# DisplayArray.net
KiCad netlist of a schematic drawn in EAGLE
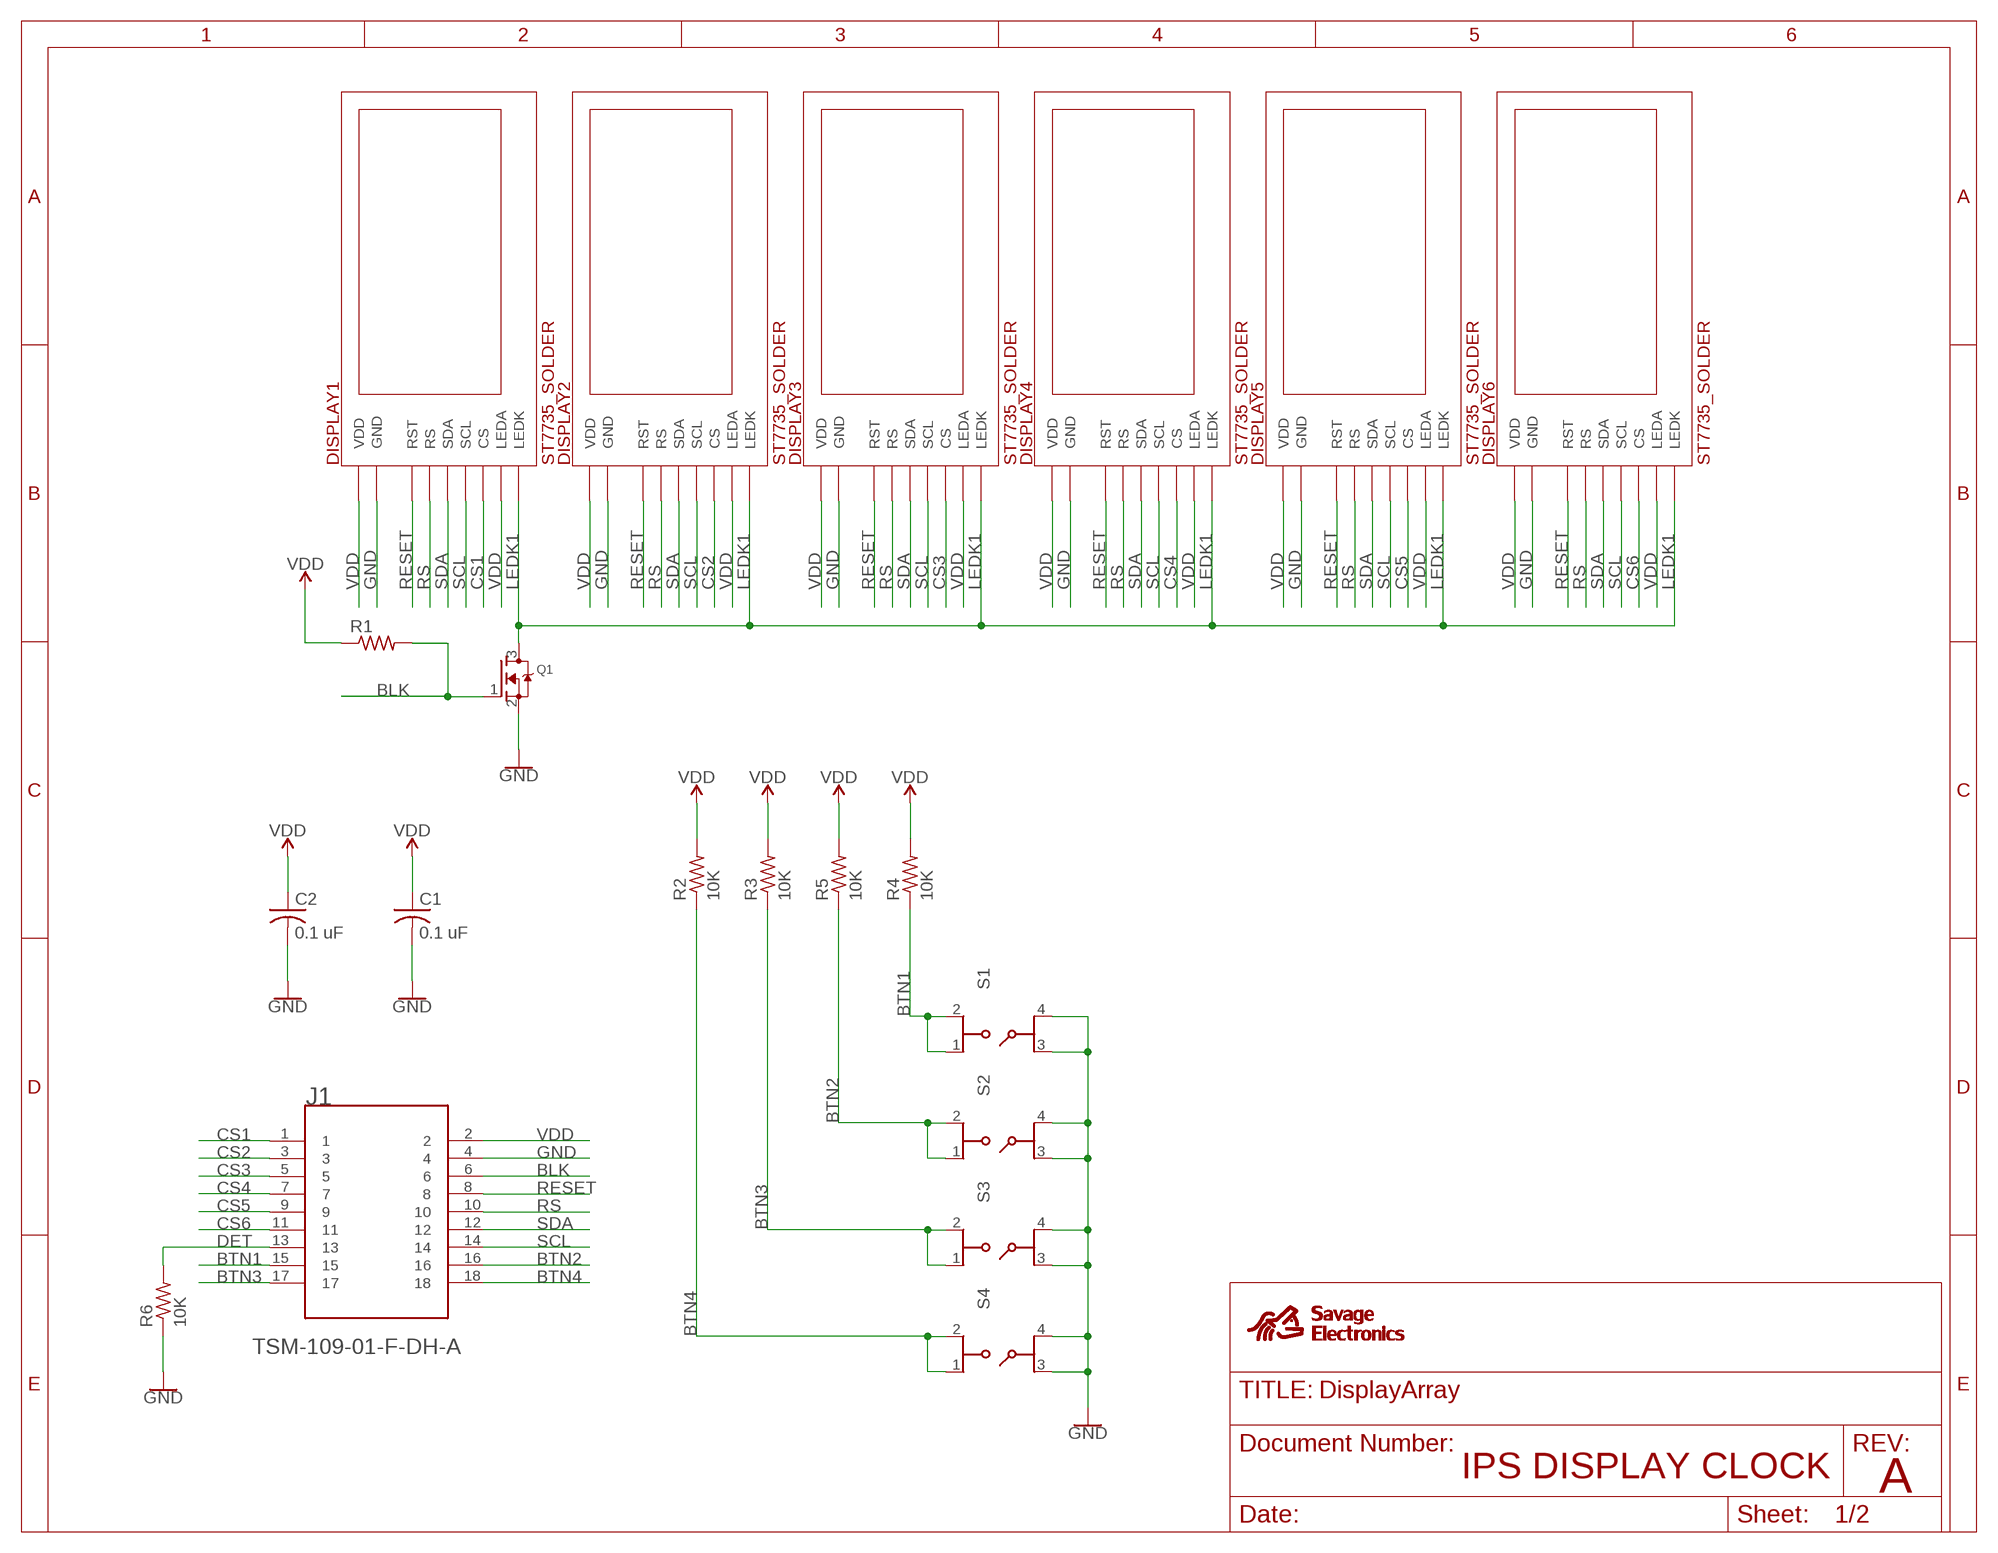
[diagram p0: schematic, sheet 1]

(export (version "E")
  (design (tool "Eeschema 10.0.6"))
  (components
    (comp (ref "C1")
      (value "0.1 uF")
      (footprint "eagle-import:C0603")
      (libsource (lib "eagle-import") (part "C-USC0603"))
    )
    (comp (ref "C2")
      (value "0.1 uF")
      (footprint "eagle-import:C0603")
      (libsource (lib "eagle-import") (part "C-USC0603"))
    )
    (comp (ref "DISPLAY1")
      (value "ST7735_SOLDER")
      (footprint "eagle-import:IPSLCD096_SOLDER")
      (libsource (lib "eagle-import") (part "ST7735_SOLDER"))
    )
    (comp (ref "DISPLAY2")
      (value "ST7735_SOLDER")
      (footprint "eagle-import:IPSLCD096_SOLDER")
      (libsource (lib "eagle-import") (part "ST7735_SOLDER"))
    )
    (comp (ref "DISPLAY3")
      (value "ST7735_SOLDER")
      (footprint "eagle-import:IPSLCD096_SOLDER")
      (libsource (lib "eagle-import") (part "ST7735_SOLDER"))
    )
    (comp (ref "DISPLAY4")
      (value "ST7735_SOLDER")
      (footprint "eagle-import:IPSLCD096_SOLDER")
      (libsource (lib "eagle-import") (part "ST7735_SOLDER"))
    )
    (comp (ref "DISPLAY5")
      (value "ST7735_SOLDER")
      (footprint "eagle-import:IPSLCD096_SOLDER")
      (libsource (lib "eagle-import") (part "ST7735_SOLDER"))
    )
    (comp (ref "DISPLAY6")
      (value "ST7735_SOLDER")
      (footprint "eagle-import:IPSLCD096_SOLDER")
      (libsource (lib "eagle-import") (part "ST7735_SOLDER"))
    )
    (comp (ref "J1")
      (value "TSM-109-01-F-DH-A")
      (footprint "eagle-import:SAMTEC-TSM-109-02-X-DH-A")
      (libsource (lib "eagle-import") (part "SAMTEC-TSM-109-02-X-DH-AJ"))
    )
    (comp (ref "Q1")
      (value "MOSFET-NREFLOW")
      (footprint "eagle-import:SOT23")
      (libsource (lib "eagle-import") (part "MOSFET-NREFLOW"))
    )
    (comp (ref "R1")
      (value "R-US_R0805")
      (footprint "eagle-import:R0805")
      (libsource (lib "eagle-import") (part "R-US_R0805"))
    )
    (comp (ref "R2")
      (value "10K")
      (footprint "eagle-import:R0805")
      (libsource (lib "eagle-import") (part "R-US_R0805"))
    )
    (comp (ref "R3")
      (value "10K")
      (footprint "eagle-import:R0805")
      (libsource (lib "eagle-import") (part "R-US_R0805"))
    )
    (comp (ref "R4")
      (value "10K")
      (footprint "eagle-import:R0805")
      (libsource (lib "eagle-import") (part "R-US_R0805"))
    )
    (comp (ref "R5")
      (value "10K")
      (footprint "eagle-import:R0805")
      (libsource (lib "eagle-import") (part "R-US_R0805"))
    )
    (comp (ref "R6")
      (value "10K")
      (footprint "eagle-import:R0805")
      (libsource (lib "eagle-import") (part "R-US_R0805"))
    )
    (comp (ref "S1")
      (value "434123025826")
      (footprint "eagle-import:434123025826")
      (libsource (lib "eagle-import") (part "434123025826"))
    )
    (comp (ref "S2")
      (value "434123025826")
      (footprint "eagle-import:434123025826")
      (libsource (lib "eagle-import") (part "434123025826"))
    )
    (comp (ref "S3")
      (value "434123025826")
      (footprint "eagle-import:434123025826")
      (libsource (lib "eagle-import") (part "434123025826"))
    )
    (comp (ref "S4")
      (value "434123025826")
      (footprint "eagle-import:434123025826")
      (libsource (lib "eagle-import") (part "434123025826"))
    )
    (comp (ref "U$3")
      (value "SE_SMALL_SILK")
      (footprint "eagle-import:SE_SMALL_SILK")
      (libsource (lib "eagle-import") (part "SE_SMALL_SILK"))
    )
  )
  (nets
    (net (code "1") (name "BLK") (class "Default")
      (node (ref "J1") (pin "6") (pinfunction "6_6") (pintype "passive"))
      (node (ref "Q1") (pin "1") (pinfunction "G_1") (pintype "bidirectional"))
      (node (ref "R1") (pin "2") (pinfunction "2_2") (pintype "passive"))
    )
    (net (code "2") (name "BTN1") (class "Default")
      (node (ref "J1") (pin "15") (pinfunction "15_15") (pintype "passive"))
      (node (ref "R4") (pin "1") (pinfunction "1_1") (pintype "passive"))
      (node (ref "S1") (pin "1") (pinfunction "1_1") (pintype "passive"))
      (node (ref "S1") (pin "2") (pinfunction "2_2") (pintype "passive"))
    )
    (net (code "3") (name "BTN2") (class "Default")
      (node (ref "J1") (pin "16") (pinfunction "16_16") (pintype "passive"))
      (node (ref "R5") (pin "1") (pinfunction "1_1") (pintype "passive"))
      (node (ref "S2") (pin "1") (pinfunction "1_1") (pintype "passive"))
      (node (ref "S2") (pin "2") (pinfunction "2_2") (pintype "passive"))
    )
    (net (code "4") (name "BTN3") (class "Default")
      (node (ref "J1") (pin "17") (pinfunction "17_17") (pintype "passive"))
      (node (ref "R3") (pin "1") (pinfunction "1_1") (pintype "passive"))
      (node (ref "S3") (pin "1") (pinfunction "1_1") (pintype "passive"))
      (node (ref "S3") (pin "2") (pinfunction "2_2") (pintype "passive"))
    )
    (net (code "5") (name "BTN4") (class "Default")
      (node (ref "J1") (pin "18") (pinfunction "18_18") (pintype "passive"))
      (node (ref "R2") (pin "1") (pinfunction "1_1") (pintype "passive"))
      (node (ref "S4") (pin "1") (pinfunction "1_1") (pintype "passive"))
      (node (ref "S4") (pin "2") (pinfunction "2_2") (pintype "passive"))
    )
    (net (code "6") (name "CS1") (class "Default")
      (node (ref "DISPLAY1") (pin "7") (pinfunction "CS_7") (pintype "bidirectional"))
      (node (ref "J1") (pin "1") (pinfunction "1_1") (pintype "passive"))
    )
    (net (code "7") (name "CS2") (class "Default")
      (node (ref "DISPLAY2") (pin "7") (pinfunction "CS_7") (pintype "bidirectional"))
      (node (ref "J1") (pin "3") (pinfunction "3_3") (pintype "passive"))
    )
    (net (code "8") (name "CS3") (class "Default")
      (node (ref "DISPLAY3") (pin "7") (pinfunction "CS_7") (pintype "bidirectional"))
      (node (ref "J1") (pin "5") (pinfunction "5_5") (pintype "passive"))
    )
    (net (code "9") (name "CS4") (class "Default")
      (node (ref "DISPLAY4") (pin "7") (pinfunction "CS_7") (pintype "bidirectional"))
      (node (ref "J1") (pin "7") (pinfunction "7_7") (pintype "passive"))
    )
    (net (code "10") (name "CS5") (class "Default")
      (node (ref "DISPLAY5") (pin "7") (pinfunction "CS_7") (pintype "bidirectional"))
      (node (ref "J1") (pin "9") (pinfunction "9_9") (pintype "passive"))
    )
    (net (code "11") (name "CS6") (class "Default")
      (node (ref "DISPLAY6") (pin "7") (pinfunction "CS_7") (pintype "bidirectional"))
      (node (ref "J1") (pin "11") (pinfunction "11_11") (pintype "passive"))
    )
    (net (code "12") (name "DET") (class "Default")
      (node (ref "J1") (pin "13") (pinfunction "13_13") (pintype "passive"))
      (node (ref "R6") (pin "2") (pinfunction "2_2") (pintype "passive"))
    )
    (net (code "13") (name "GND") (class "Default")
      (node (ref "C1") (pin "2") (pinfunction "2_2") (pintype "passive"))
      (node (ref "C2") (pin "2") (pinfunction "2_2") (pintype "passive"))
      (node (ref "DISPLAY1") (pin "13") (pinfunction "GND_13") (pintype "bidirectional"))
      (node (ref "DISPLAY1") (pin "8") (pinfunction "GND_8") (pintype "bidirectional"))
      (node (ref "DISPLAY2") (pin "13") (pinfunction "GND_13") (pintype "bidirectional"))
      (node (ref "DISPLAY2") (pin "8") (pinfunction "GND_8") (pintype "bidirectional"))
      (node (ref "DISPLAY3") (pin "13") (pinfunction "GND_13") (pintype "bidirectional"))
      (node (ref "DISPLAY3") (pin "8") (pinfunction "GND_8") (pintype "bidirectional"))
      (node (ref "DISPLAY4") (pin "13") (pinfunction "GND_13") (pintype "bidirectional"))
      (node (ref "DISPLAY4") (pin "8") (pinfunction "GND_8") (pintype "bidirectional"))
      (node (ref "DISPLAY5") (pin "13") (pinfunction "GND_13") (pintype "bidirectional"))
      (node (ref "DISPLAY5") (pin "8") (pinfunction "GND_8") (pintype "bidirectional"))
      (node (ref "DISPLAY6") (pin "13") (pinfunction "GND_13") (pintype "bidirectional"))
      (node (ref "DISPLAY6") (pin "8") (pinfunction "GND_8") (pintype "bidirectional"))
      (node (ref "J1") (pin "4") (pinfunction "4_4") (pintype "passive"))
      (node (ref "Q1") (pin "2") (pinfunction "S_2") (pintype "bidirectional"))
      (node (ref "R6") (pin "1") (pinfunction "1_1") (pintype "passive"))
      (node (ref "S1") (pin "3") (pinfunction "3_3") (pintype "passive"))
      (node (ref "S1") (pin "4") (pinfunction "4_4") (pintype "passive"))
      (node (ref "S2") (pin "3") (pinfunction "3_3") (pintype "passive"))
      (node (ref "S2") (pin "4") (pinfunction "4_4") (pintype "passive"))
      (node (ref "S3") (pin "3") (pinfunction "3_3") (pintype "passive"))
      (node (ref "S3") (pin "4") (pinfunction "4_4") (pintype "passive"))
      (node (ref "S4") (pin "3") (pinfunction "3_3") (pintype "passive"))
      (node (ref "S4") (pin "4") (pinfunction "4_4") (pintype "passive"))
    )
    (net (code "14") (name "LEDK1") (class "Default")
      (node (ref "DISPLAY1") (pin "11") (pinfunction "LEDK_11") (pintype "bidirectional"))
      (node (ref "DISPLAY2") (pin "11") (pinfunction "LEDK_11") (pintype "bidirectional"))
      (node (ref "DISPLAY3") (pin "11") (pinfunction "LEDK_11") (pintype "bidirectional"))
      (node (ref "DISPLAY4") (pin "11") (pinfunction "LEDK_11") (pintype "bidirectional"))
      (node (ref "DISPLAY5") (pin "11") (pinfunction "LEDK_11") (pintype "bidirectional"))
      (node (ref "DISPLAY6") (pin "11") (pinfunction "LEDK_11") (pintype "bidirectional"))
      (node (ref "Q1") (pin "3") (pinfunction "D_3") (pintype "bidirectional"))
    )
    (net (code "15") (name "RESET") (class "Default")
      (node (ref "DISPLAY1") (pin "6") (pinfunction "RST_6") (pintype "bidirectional"))
      (node (ref "DISPLAY2") (pin "6") (pinfunction "RST_6") (pintype "bidirectional"))
      (node (ref "DISPLAY3") (pin "6") (pinfunction "RST_6") (pintype "bidirectional"))
      (node (ref "DISPLAY4") (pin "6") (pinfunction "RST_6") (pintype "bidirectional"))
      (node (ref "DISPLAY5") (pin "6") (pinfunction "RST_6") (pintype "bidirectional"))
      (node (ref "DISPLAY6") (pin "6") (pinfunction "RST_6") (pintype "bidirectional"))
      (node (ref "J1") (pin "8") (pinfunction "8_8") (pintype "passive"))
    )
    (net (code "16") (name "RS") (class "Default")
      (node (ref "DISPLAY1") (pin "5") (pinfunction "RS_5") (pintype "bidirectional"))
      (node (ref "DISPLAY2") (pin "5") (pinfunction "RS_5") (pintype "bidirectional"))
      (node (ref "DISPLAY3") (pin "5") (pinfunction "RS_5") (pintype "bidirectional"))
      (node (ref "DISPLAY4") (pin "5") (pinfunction "RS_5") (pintype "bidirectional"))
      (node (ref "DISPLAY5") (pin "5") (pinfunction "RS_5") (pintype "bidirectional"))
      (node (ref "DISPLAY6") (pin "5") (pinfunction "RS_5") (pintype "bidirectional"))
      (node (ref "J1") (pin "10") (pinfunction "10_10") (pintype "passive"))
    )
    (net (code "17") (name "SCL") (class "Default")
      (node (ref "DISPLAY1") (pin "4") (pinfunction "SCL_4") (pintype "bidirectional"))
      (node (ref "DISPLAY2") (pin "4") (pinfunction "SCL_4") (pintype "bidirectional"))
      (node (ref "DISPLAY3") (pin "4") (pinfunction "SCL_4") (pintype "bidirectional"))
      (node (ref "DISPLAY4") (pin "4") (pinfunction "SCL_4") (pintype "bidirectional"))
      (node (ref "DISPLAY5") (pin "4") (pinfunction "SCL_4") (pintype "bidirectional"))
      (node (ref "DISPLAY6") (pin "4") (pinfunction "SCL_4") (pintype "bidirectional"))
      (node (ref "J1") (pin "14") (pinfunction "14_14") (pintype "passive"))
    )
    (net (code "18") (name "SDA") (class "Default")
      (node (ref "DISPLAY1") (pin "3") (pinfunction "SDA_3") (pintype "bidirectional"))
      (node (ref "DISPLAY2") (pin "3") (pinfunction "SDA_3") (pintype "bidirectional"))
      (node (ref "DISPLAY3") (pin "3") (pinfunction "SDA_3") (pintype "bidirectional"))
      (node (ref "DISPLAY4") (pin "3") (pinfunction "SDA_3") (pintype "bidirectional"))
      (node (ref "DISPLAY5") (pin "3") (pinfunction "SDA_3") (pintype "bidirectional"))
      (node (ref "DISPLAY6") (pin "3") (pinfunction "SDA_3") (pintype "bidirectional"))
      (node (ref "J1") (pin "12") (pinfunction "12_12") (pintype "passive"))
    )
    (net (code "19") (name "VDD") (class "Default")
      (node (ref "C1") (pin "1") (pinfunction "1_1") (pintype "passive"))
      (node (ref "C2") (pin "1") (pinfunction "1_1") (pintype "passive"))
      (node (ref "DISPLAY1") (pin "10") (pinfunction "VDD_10") (pintype "bidirectional"))
      (node (ref "DISPLAY1") (pin "12") (pinfunction "LEDA_12") (pintype "bidirectional"))
      (node (ref "DISPLAY2") (pin "10") (pinfunction "VDD_10") (pintype "bidirectional"))
      (node (ref "DISPLAY2") (pin "12") (pinfunction "LEDA_12") (pintype "bidirectional"))
      (node (ref "DISPLAY3") (pin "10") (pinfunction "VDD_10") (pintype "bidirectional"))
      (node (ref "DISPLAY3") (pin "12") (pinfunction "LEDA_12") (pintype "bidirectional"))
      (node (ref "DISPLAY4") (pin "10") (pinfunction "VDD_10") (pintype "bidirectional"))
      (node (ref "DISPLAY4") (pin "12") (pinfunction "LEDA_12") (pintype "bidirectional"))
      (node (ref "DISPLAY5") (pin "10") (pinfunction "VDD_10") (pintype "bidirectional"))
      (node (ref "DISPLAY5") (pin "12") (pinfunction "LEDA_12") (pintype "bidirectional"))
      (node (ref "DISPLAY6") (pin "10") (pinfunction "VDD_10") (pintype "bidirectional"))
      (node (ref "DISPLAY6") (pin "12") (pinfunction "LEDA_12") (pintype "bidirectional"))
      (node (ref "J1") (pin "2") (pinfunction "2_2") (pintype "passive"))
      (node (ref "R1") (pin "1") (pinfunction "1_1") (pintype "passive"))
      (node (ref "R2") (pin "2") (pinfunction "2_2") (pintype "passive"))
      (node (ref "R3") (pin "2") (pinfunction "2_2") (pintype "passive"))
      (node (ref "R4") (pin "2") (pinfunction "2_2") (pintype "passive"))
      (node (ref "R5") (pin "2") (pinfunction "2_2") (pintype "passive"))
    )
  )
)
